# 14_-_SPI_FLASH_LEDS.net
KiCad netlist of a schematic drawn in Altium Designer
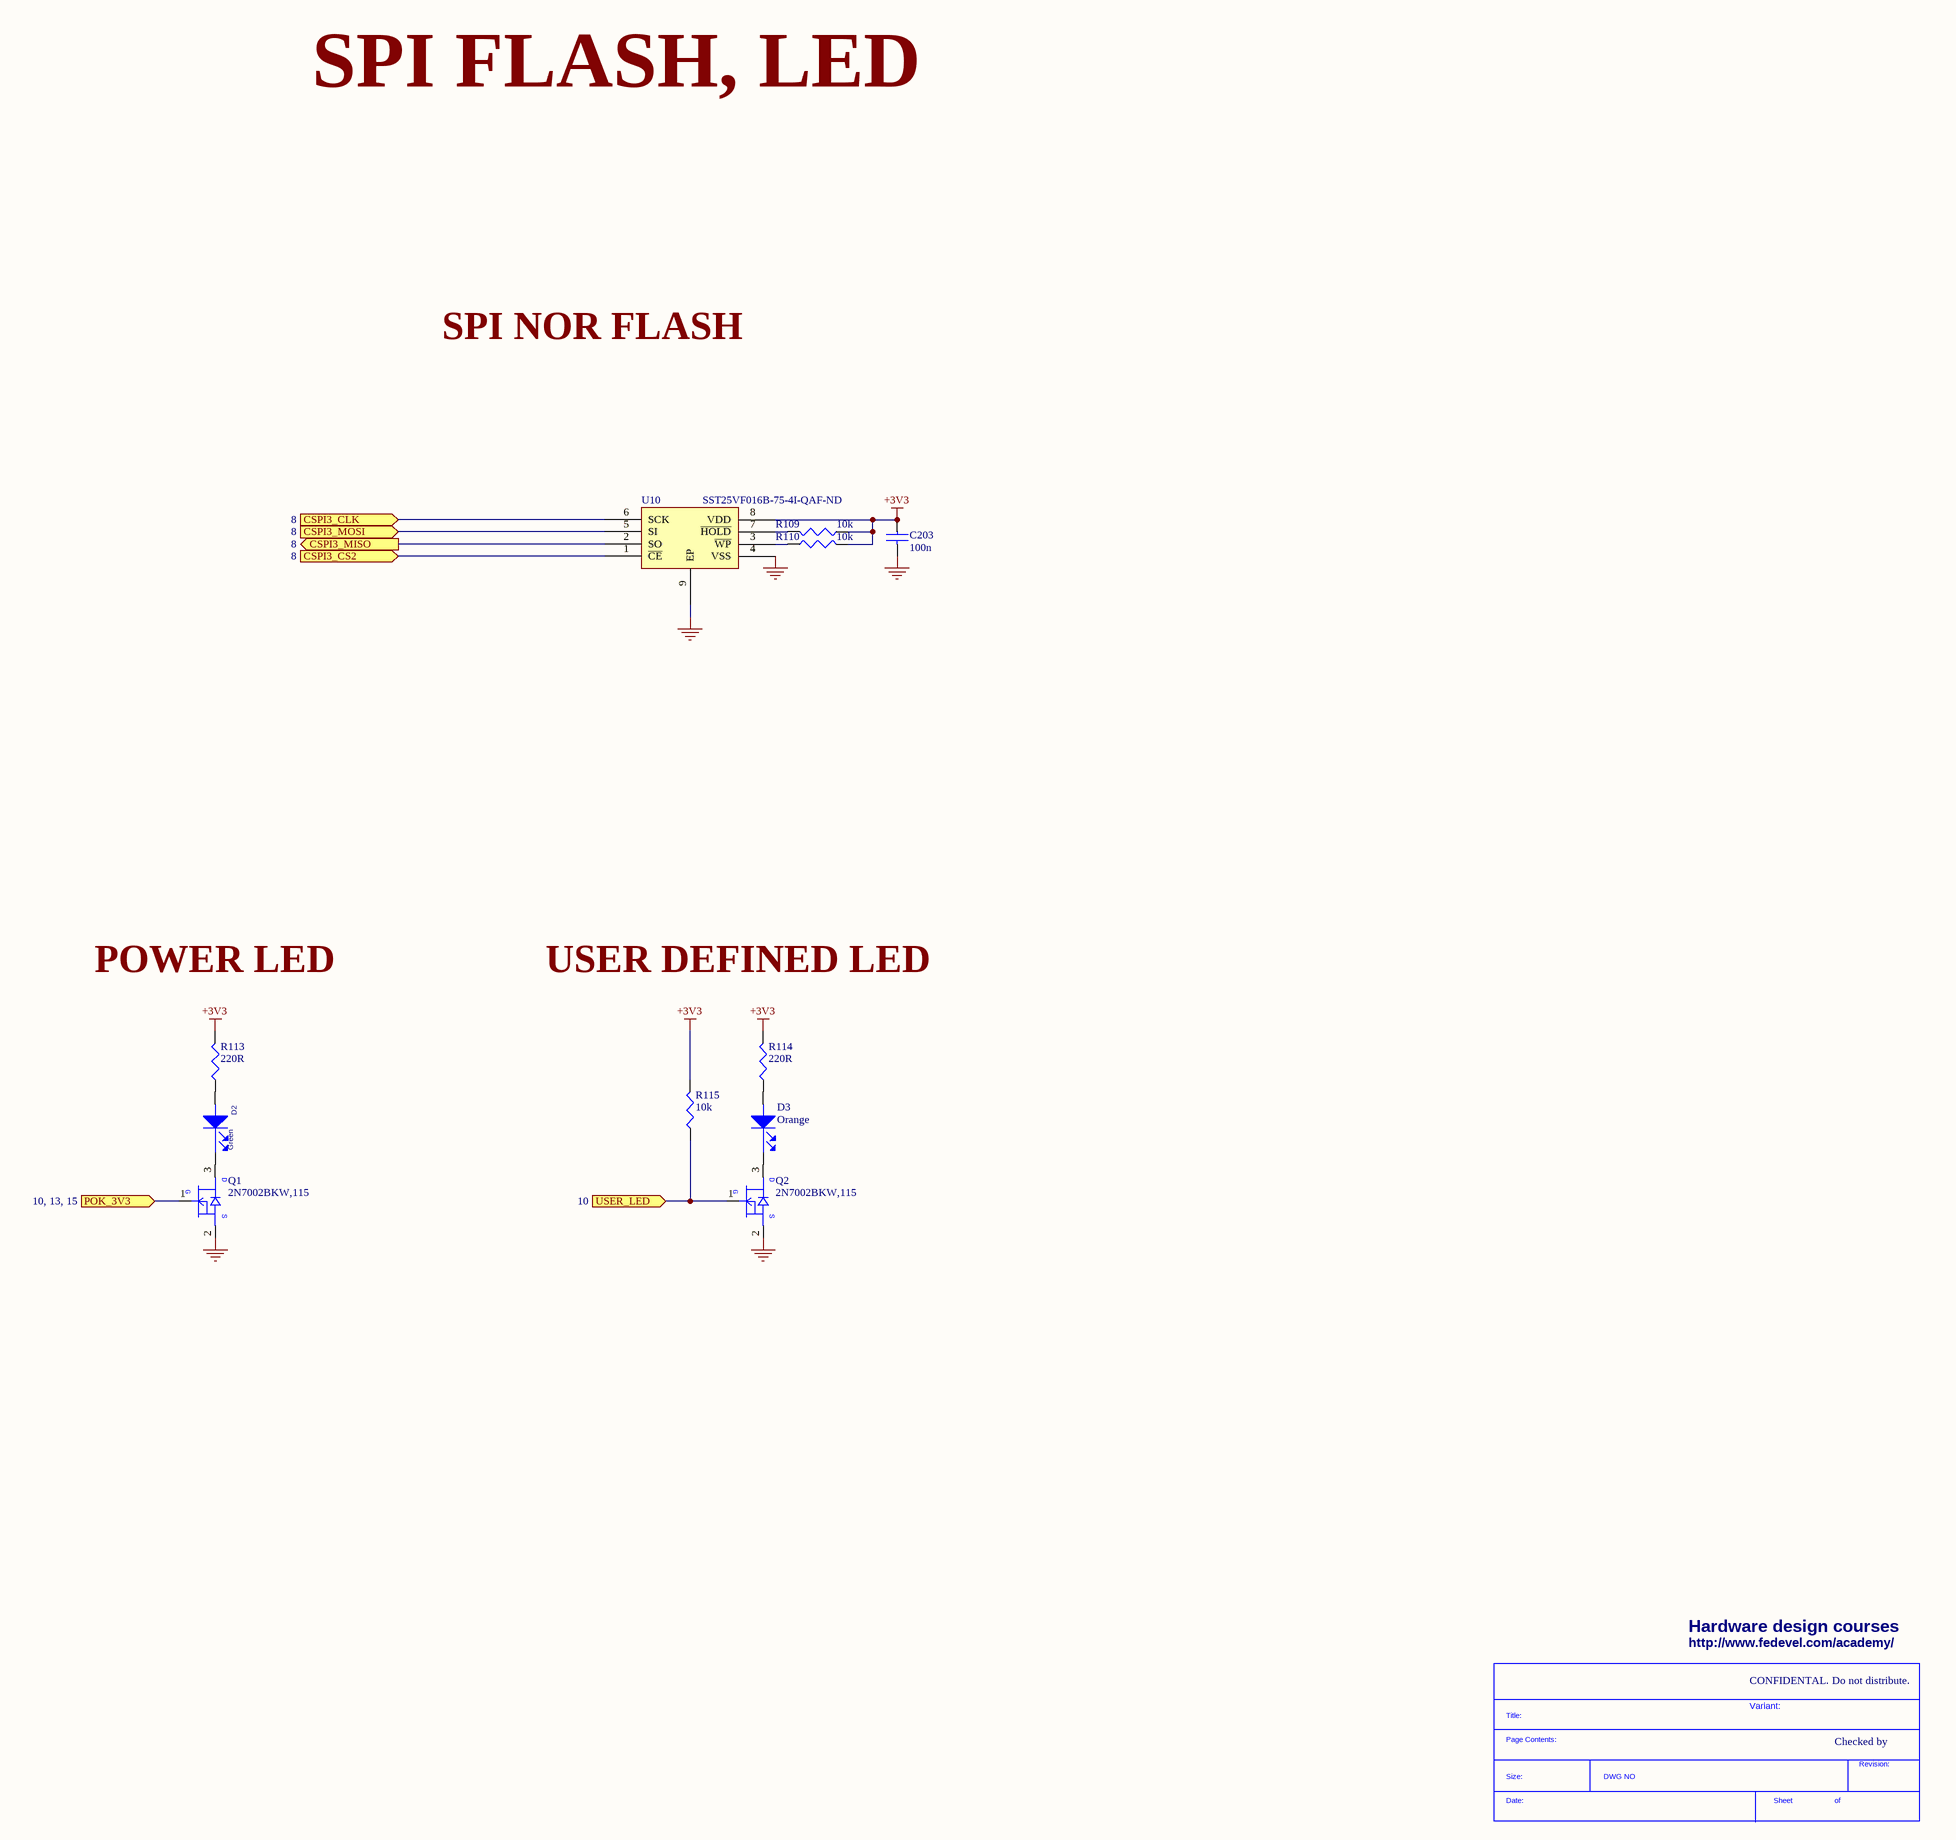
[diagram p0: [14] - SPI FLASH, LEDS.SchDoc]

(export (version "E")
  (design (tool "Eeschema 10.0.6"))
  (components
    (comp (ref "C203")
      (value "100n")
      (footprint "C0402")
      (description "CAP CER .10UF 50V X5R 10% 0402")
      (fields
        (field (name "MANUFACTURER") "TDK Corporation")
        (field (name "MANUFACTURER PART NUMBER") "C1005X5R1H104K")
      )
      (libsource (lib "Integrated_Library_RF_FEB_2012") (part "C1005X5R1H104K"))
    )
    (comp (ref "D2")
      (value "Green")
      (footprint "LED_0603")
      (description "LED SMARTLED GREEN 570NM 0603")
      (fields
        (field (name "MANUFACTURER") "OSRAM Opto Semiconductors Inc")
        (field (name "MANUFACTURER PART NUMBER") "LG L29K-G2J1-24-Z")
      )
      (libsource (lib "Integrated_Library_RF_FEB_2012") (part "LG L29K-G2J1-24-Z"))
    )
    (comp (ref "D3")
      (value "Orange")
      (footprint "LED_0603")
      (description "LED SMARTLED ORANGE 606NM 0603")
      (fields
        (field (name "MANUFACTURER") "OSRAM Opto Semiconductors Inc")
        (field (name "MANUFACTURER PART NUMBER") "LO L29K-H2K1-24-Z")
        (field (name ".CHECKED PCB") "RF")
        (field (name ".CHECKED SCH") "RF")
      )
      (libsource (lib "Integrated_Library_RF_FEB_2012") (part "LO L29K-H2K1-24-Z"))
    )
    (comp (ref "Q1")
      (value "2N7002BKW,115")
      (footprint "SC70_SOT323")
      (description "MOSFET N-CH 60V 310MA SOT323")
      (fields
        (field (name "MANUFACTURER") "NXP Semiconductors")
        (field (name ".CHECKED PCB") "RF")
        (field (name ".CHECKED SCH") "RF")
      )
      (libsource (lib "Integrated_Library_RF_FEB_2012") (part "2N7002BKW,115"))
    )
    (comp (ref "Q2")
      (value "2N7002BKW,115")
      (footprint "SC70_SOT323")
      (description "MOSFET N-CH 60V 310MA SOT323")
      (fields
        (field (name "MANUFACTURER") "NXP Semiconductors")
        (field (name ".CHECKED PCB") "RF")
        (field (name ".CHECKED SCH") "RF")
      )
      (libsource (lib "Integrated_Library_RF_FEB_2012") (part "2N7002BKW,115"))
    )
    (comp (ref "R109")
      (value "10k")
      (footprint "R0402")
      (description "RES 10.0K OHM 1/16W 1% 0402 SMD")
      (fields
        (field (name "MANUFACTURER") "Yageo")
        (field (name "MANUFACTURER PART NUMBER") "RC0402FR-0710KL")
      )
      (libsource (lib "Integrated_Library_RF_FEB_2012") (part "RC0402FR-0710KL"))
    )
    (comp (ref "R110")
      (value "10k")
      (footprint "R0402")
      (description "RES 10.0K OHM 1/16W 1% 0402 SMD")
      (fields
        (field (name "MANUFACTURER") "Yageo")
        (field (name "MANUFACTURER PART NUMBER") "RC0402FR-0710KL")
      )
      (libsource (lib "Integrated_Library_RF_FEB_2012") (part "RC0402FR-0710KL"))
    )
    (comp (ref "R113")
      (value "220R")
      (footprint "R0402")
      (description "RES 220 OHM 1/16W 1% 0402 SMD")
      (fields
        (field (name "MANUFACTURER") "Yageo")
        (field (name "MANUFACTURER PART NUMBER") "RC0402FR-07220RL")
      )
      (libsource (lib "Integrated_Library_RF_FEB_2012") (part "RC0402FR-07220RL"))
    )
    (comp (ref "R114")
      (value "220R")
      (footprint "R0402")
      (description "RES 220 OHM 1/16W 1% 0402 SMD")
      (fields
        (field (name "MANUFACTURER") "Yageo")
        (field (name "MANUFACTURER PART NUMBER") "RC0402FR-07220RL")
      )
      (libsource (lib "Integrated_Library_RF_FEB_2012") (part "RC0402FR-07220RL"))
    )
    (comp (ref "R115")
      (value "10k")
      (footprint "R0402")
      (description "RES 10.0K OHM 1/16W 1% 0402 SMD")
      (fields
        (field (name "MANUFACTURER") "Yageo")
        (field (name "MANUFACTURER PART NUMBER") "RC0402FR-0710KL")
      )
      (libsource (lib "Integrated_Library_RF_FEB_2012") (part "RC0402FR-0710KL"))
    )
    (comp (ref "U10")
      (value "SST25VF016B-75-4I-QAF-ND")
      (footprint "WSON8_6X5MM")
      (description "IC FLASH 16MBIT 75MHZ 8WSON")
      (fields
        (field (name "MANUFACTURER") "Microchip Technology")
        (field (name "MANUFACTURER PART NUMBER") "SST25VF016B-75-4I-QAF")
        (field (name ".CREATOR") "MM")
        (field (name ".CHECKED PCB") "MM, checked by RF")
        (field (name ".CHECKED SCH") "MM, checked by RF")
      )
      (libsource (lib "Schlib_RF") (part "SST25VF016B-75-4I-QAF"))
    )
  )
  (nets
    (net (code "1") (name "+3V3") (class "Default")
      (node (ref "C203") (pin "1") (pinfunction "1_1") (pintype "passive"))
      (node (ref "R109") (pin "1") (pinfunction "1_1") (pintype "passive"))
      (node (ref "R110") (pin "2") (pinfunction "2_2") (pintype "passive"))
      (node (ref "R113") (pin "2") (pinfunction "2_2") (pintype "passive"))
      (node (ref "R114") (pin "2") (pinfunction "2_2") (pintype "passive"))
      (node (ref "R115") (pin "2") (pinfunction "2_2") (pintype "passive"))
      (node (ref "U10") (pin "8") (pinfunction "VDD_8") (pintype "passive"))
    )
    (net (code "2") (name "/CSPI3_CLK") (class "Default")
      (node (ref "U10") (pin "6") (pinfunction "SCK_6") (pintype "passive"))
    )
    (net (code "3") (name "/CSPI3_CS2") (class "Default")
      (node (ref "U10") (pin "1") (pinfunction "~{CE}_1") (pintype "passive"))
    )
    (net (code "4") (name "/CSPI3_MISO") (class "Default")
      (node (ref "U10") (pin "2") (pinfunction "SO_2") (pintype "passive"))
    )
    (net (code "5") (name "/CSPI3_MOSI") (class "Default")
      (node (ref "U10") (pin "5") (pinfunction "SI_5") (pintype "passive"))
    )
    (net (code "6") (name "/POK_3V3") (class "Default")
      (node (ref "Q1") (pin "1") (pinfunction "GATE_1") (pintype "passive"))
    )
    (net (code "7") (name "/USER_LED") (class "Default")
      (node (ref "Q2") (pin "1") (pinfunction "GATE_1") (pintype "passive"))
      (node (ref "R115") (pin "1") (pinfunction "1_1") (pintype "passive"))
    )
    (net (code "8") (name "GND") (class "Default")
      (node (ref "C203") (pin "2") (pinfunction "2_2") (pintype "passive"))
      (node (ref "Q1") (pin "2") (pinfunction "SOURCE_2") (pintype "passive"))
      (node (ref "Q2") (pin "2") (pinfunction "SOURCE_2") (pintype "passive"))
      (node (ref "U10") (pin "4") (pinfunction "VSS_4") (pintype "passive"))
      (node (ref "U10") (pin "9") (pinfunction "EP_9") (pintype "passive"))
    )
    (net (code "9") (name "Net-(D2-ANODE)") (class "Default")
      (node (ref "D2") (pin "2") (pinfunction "ANODE_2") (pintype "passive"))
      (node (ref "R113") (pin "1") (pinfunction "1_1") (pintype "passive"))
    )
    (net (code "10") (name "Net-(D2-cathode)") (class "Default")
      (node (ref "D2") (pin "1") (pinfunction "cathode_1") (pintype "passive"))
      (node (ref "Q1") (pin "3") (pinfunction "DRAIN_3") (pintype "passive"))
    )
    (net (code "11") (name "Net-(D3-ANODE)") (class "Default")
      (node (ref "D3") (pin "2") (pinfunction "ANODE_2") (pintype "passive"))
      (node (ref "R114") (pin "1") (pinfunction "1_1") (pintype "passive"))
    )
    (net (code "12") (name "Net-(D3-cathode)") (class "Default")
      (node (ref "D3") (pin "1") (pinfunction "cathode_1") (pintype "passive"))
      (node (ref "Q2") (pin "3") (pinfunction "DRAIN_3") (pintype "passive"))
    )
    (net (code "13") (name "Net-(U10-~{HOLD})") (class "Default")
      (node (ref "R109") (pin "2") (pinfunction "2_2") (pintype "passive"))
      (node (ref "U10") (pin "7") (pinfunction "~{HOLD}_7") (pintype "passive"))
    )
    (net (code "14") (name "Net-(U10-~{WP})") (class "Default")
      (node (ref "R110") (pin "1") (pinfunction "1_1") (pintype "passive"))
      (node (ref "U10") (pin "3") (pinfunction "~{WP}_3") (pintype "passive"))
    )
  )
)
